# plp-ctop_3c.net
KiCad netlist of a schematic drawn in Altium Designer
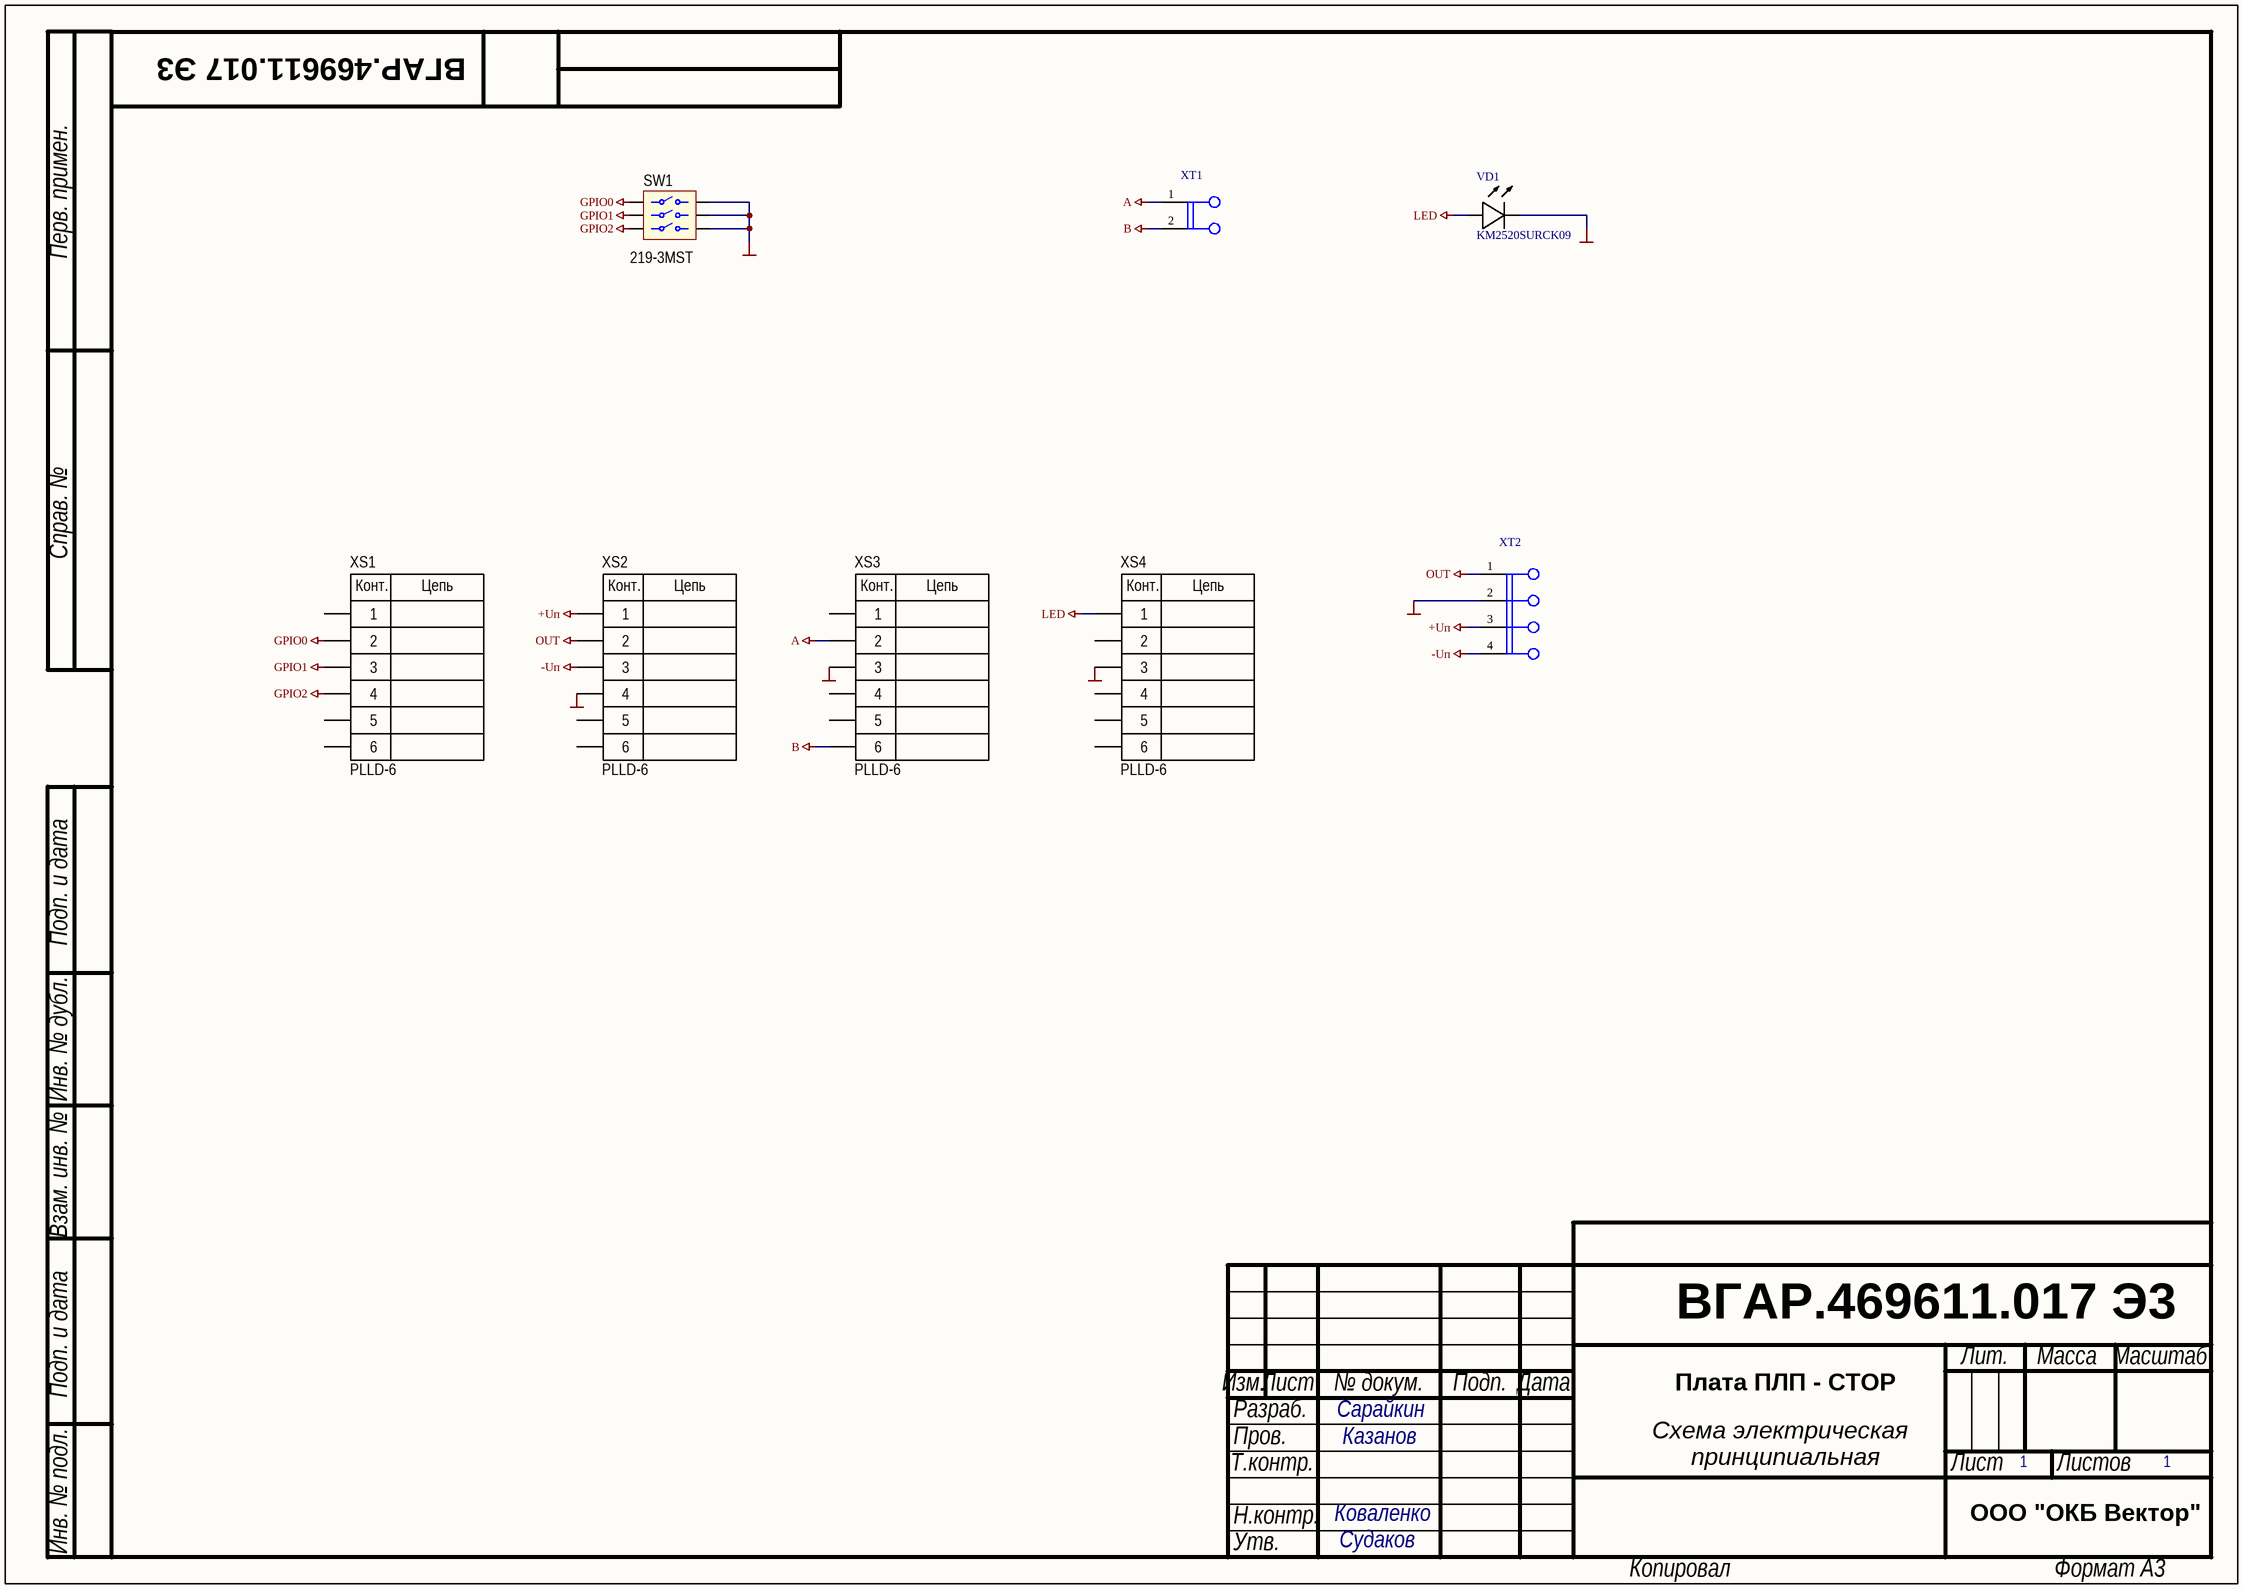
[diagram p0: plp-ctop_3c.SchDoc]

(export (version "E")
  (design (tool "Eeschema 10.0.6"))
  (components
    (comp (ref "SW1")
      (value "219-3MST")
      (footprint "219-3MST")
      (libsource (lib "electromechanics") (part "219-3MST"))
    )
    (comp (ref "VD1")
      (value "KM2520SURCK09")
      (footprint "KM2520SURCK09")
      (description "LED")
      (libsource (lib "Kingbright LED") (part "KM2520SURCK09"))
    )
    (comp (ref "XS1")
      (value "PLLD-6")
      (footprint "CON: PLL-6(2x3R1.27female)")
      (description "Step 1.27")
      (libsource (lib "connector") (part "PLLD-6(Female)"))
    )
    (comp (ref "XS2")
      (value "PLLD-6")
      (footprint "CON: PLL-6(2x3R1.27female)")
      (description "Step 1.27")
      (libsource (lib "connector") (part "PLLD-6(Female)"))
    )
    (comp (ref "XS3")
      (value "PLLD-6")
      (footprint "CON: PLL-6(2x3R1.27female)")
      (description "Step 1.27")
      (libsource (lib "connector") (part "PLLD-6(Female)"))
    )
    (comp (ref "XS4")
      (value "PLLD-6")
      (footprint "CON: PLL-6(2x3R1.27female)")
      (description "Step 1.27")
      (libsource (lib "connector") (part "PLLD-6(Female)"))
    )
    (comp (ref "XT1")
      (value "MKDS 1/2 - 3,5")
      (footprint "MKDS 1/2 - 3,5")
      (description "Клемник")
      (fields (field (name "MANUFACTURER") "Poenix Contact"))
      (libsource (lib "Phoenixcontact Terminal Block") (part "MKDS 1/2 - 3,5"))
    )
    (comp (ref "XT2")
      (value "MKDS 1/4 - 3,5")
      (footprint "MKDS 1/4 - 3,5")
      (description "Клемник")
      (fields (field (name "MANUFACTURER") "Poenix Contact"))
      (libsource (lib "Phoenixcontact Terminal Block") (part "MKDS 1/4 - 3,5"))
    )
  )
  (nets
    (net (code "1") (name "+Uп") (class "Default")
      (node (ref "XS2") (pin "1") (pinfunction "1_1") (pintype "passive"))
      (node (ref "XT2") (pin "3") (pinfunction "3_3") (pintype "passive"))
    )
    (net (code "2") (name "-Uп") (class "Default")
      (node (ref "XS2") (pin "3") (pinfunction "3_3") (pintype "passive"))
      (node (ref "XT2") (pin "4") (pinfunction "4_4") (pintype "passive"))
    )
    (net (code "3") (name "A") (class "Default")
      (node (ref "XS3") (pin "2") (pinfunction "2_2") (pintype "passive"))
      (node (ref "XT1") (pin "1") (pinfunction "1_1") (pintype "passive"))
    )
    (net (code "4") (name "B") (class "Default")
      (node (ref "XS3") (pin "6") (pinfunction "6_6") (pintype "passive"))
      (node (ref "XT1") (pin "2") (pinfunction "2_2") (pintype "passive"))
    )
    (net (code "5") (name "GND") (class "Default")
      (node (ref "SW1") (pin "4") (pinfunction "4_4") (pintype "passive"))
      (node (ref "SW1") (pin "5") (pinfunction "5_5") (pintype "passive"))
      (node (ref "SW1") (pin "6") (pinfunction "6_6") (pintype "passive"))
      (node (ref "VD1") (pin "2") (pinfunction "K_2") (pintype "passive"))
      (node (ref "XS2") (pin "4") (pinfunction "4_4") (pintype "passive"))
      (node (ref "XS3") (pin "3") (pinfunction "3_3") (pintype "passive"))
      (node (ref "XS4") (pin "3") (pinfunction "3_3") (pintype "passive"))
      (node (ref "XT2") (pin "2") (pinfunction "2_2") (pintype "passive"))
    )
    (net (code "6") (name "GPIO0") (class "Default")
      (node (ref "SW1") (pin "1") (pinfunction "1_1") (pintype "passive"))
      (node (ref "XS1") (pin "2") (pinfunction "2_2") (pintype "passive"))
    )
    (net (code "7") (name "GPIO1") (class "Default")
      (node (ref "SW1") (pin "2") (pinfunction "2_2") (pintype "passive"))
      (node (ref "XS1") (pin "3") (pinfunction "3_3") (pintype "passive"))
    )
    (net (code "8") (name "GPIO2") (class "Default")
      (node (ref "SW1") (pin "3") (pinfunction "3_3") (pintype "passive"))
      (node (ref "XS1") (pin "4") (pinfunction "4_4") (pintype "passive"))
    )
    (net (code "9") (name "LED") (class "Default")
      (node (ref "VD1") (pin "1") (pinfunction "A_1") (pintype "passive"))
      (node (ref "XS4") (pin "1") (pinfunction "1_1") (pintype "passive"))
    )
    (net (code "10") (name "OUT") (class "Default")
      (node (ref "XS2") (pin "2") (pinfunction "2_2") (pintype "passive"))
      (node (ref "XT2") (pin "1") (pinfunction "1_1") (pintype "passive"))
    )
    (net (code "11") (name "unconnected-(XS1-Pad1)") (class "Default")
      (node (ref "XS1") (pin "1") (pinfunction "1_1") (pintype "passive"))
    )
    (net (code "12") (name "unconnected-(XS1-Pad5)") (class "Default")
      (node (ref "XS1") (pin "5") (pinfunction "5_5") (pintype "passive"))
    )
    (net (code "13") (name "unconnected-(XS1-Pad6)") (class "Default")
      (node (ref "XS1") (pin "6") (pinfunction "6_6") (pintype "passive"))
    )
    (net (code "14") (name "unconnected-(XS2-Pad5)") (class "Default")
      (node (ref "XS2") (pin "5") (pinfunction "5_5") (pintype "passive"))
    )
    (net (code "15") (name "unconnected-(XS2-Pad6)") (class "Default")
      (node (ref "XS2") (pin "6") (pinfunction "6_6") (pintype "passive"))
    )
    (net (code "16") (name "unconnected-(XS3-Pad1)") (class "Default")
      (node (ref "XS3") (pin "1") (pinfunction "1_1") (pintype "passive"))
    )
    (net (code "17") (name "unconnected-(XS3-Pad4)") (class "Default")
      (node (ref "XS3") (pin "4") (pinfunction "4_4") (pintype "passive"))
    )
    (net (code "18") (name "unconnected-(XS3-Pad5)") (class "Default")
      (node (ref "XS3") (pin "5") (pinfunction "5_5") (pintype "passive"))
    )
    (net (code "19") (name "unconnected-(XS4-Pad2)") (class "Default")
      (node (ref "XS4") (pin "2") (pinfunction "2_2") (pintype "passive"))
    )
    (net (code "20") (name "unconnected-(XS4-Pad4)") (class "Default")
      (node (ref "XS4") (pin "4") (pinfunction "4_4") (pintype "passive"))
    )
    (net (code "21") (name "unconnected-(XS4-Pad5)") (class "Default")
      (node (ref "XS4") (pin "5") (pinfunction "5_5") (pintype "passive"))
    )
    (net (code "22") (name "unconnected-(XS4-Pad6)") (class "Default")
      (node (ref "XS4") (pin "6") (pinfunction "6_6") (pintype "passive"))
    )
  )
)
